# esp32-poe-thermocouple-hat-prod.net
KiCad netlist of a schematic drawn in EAGLE
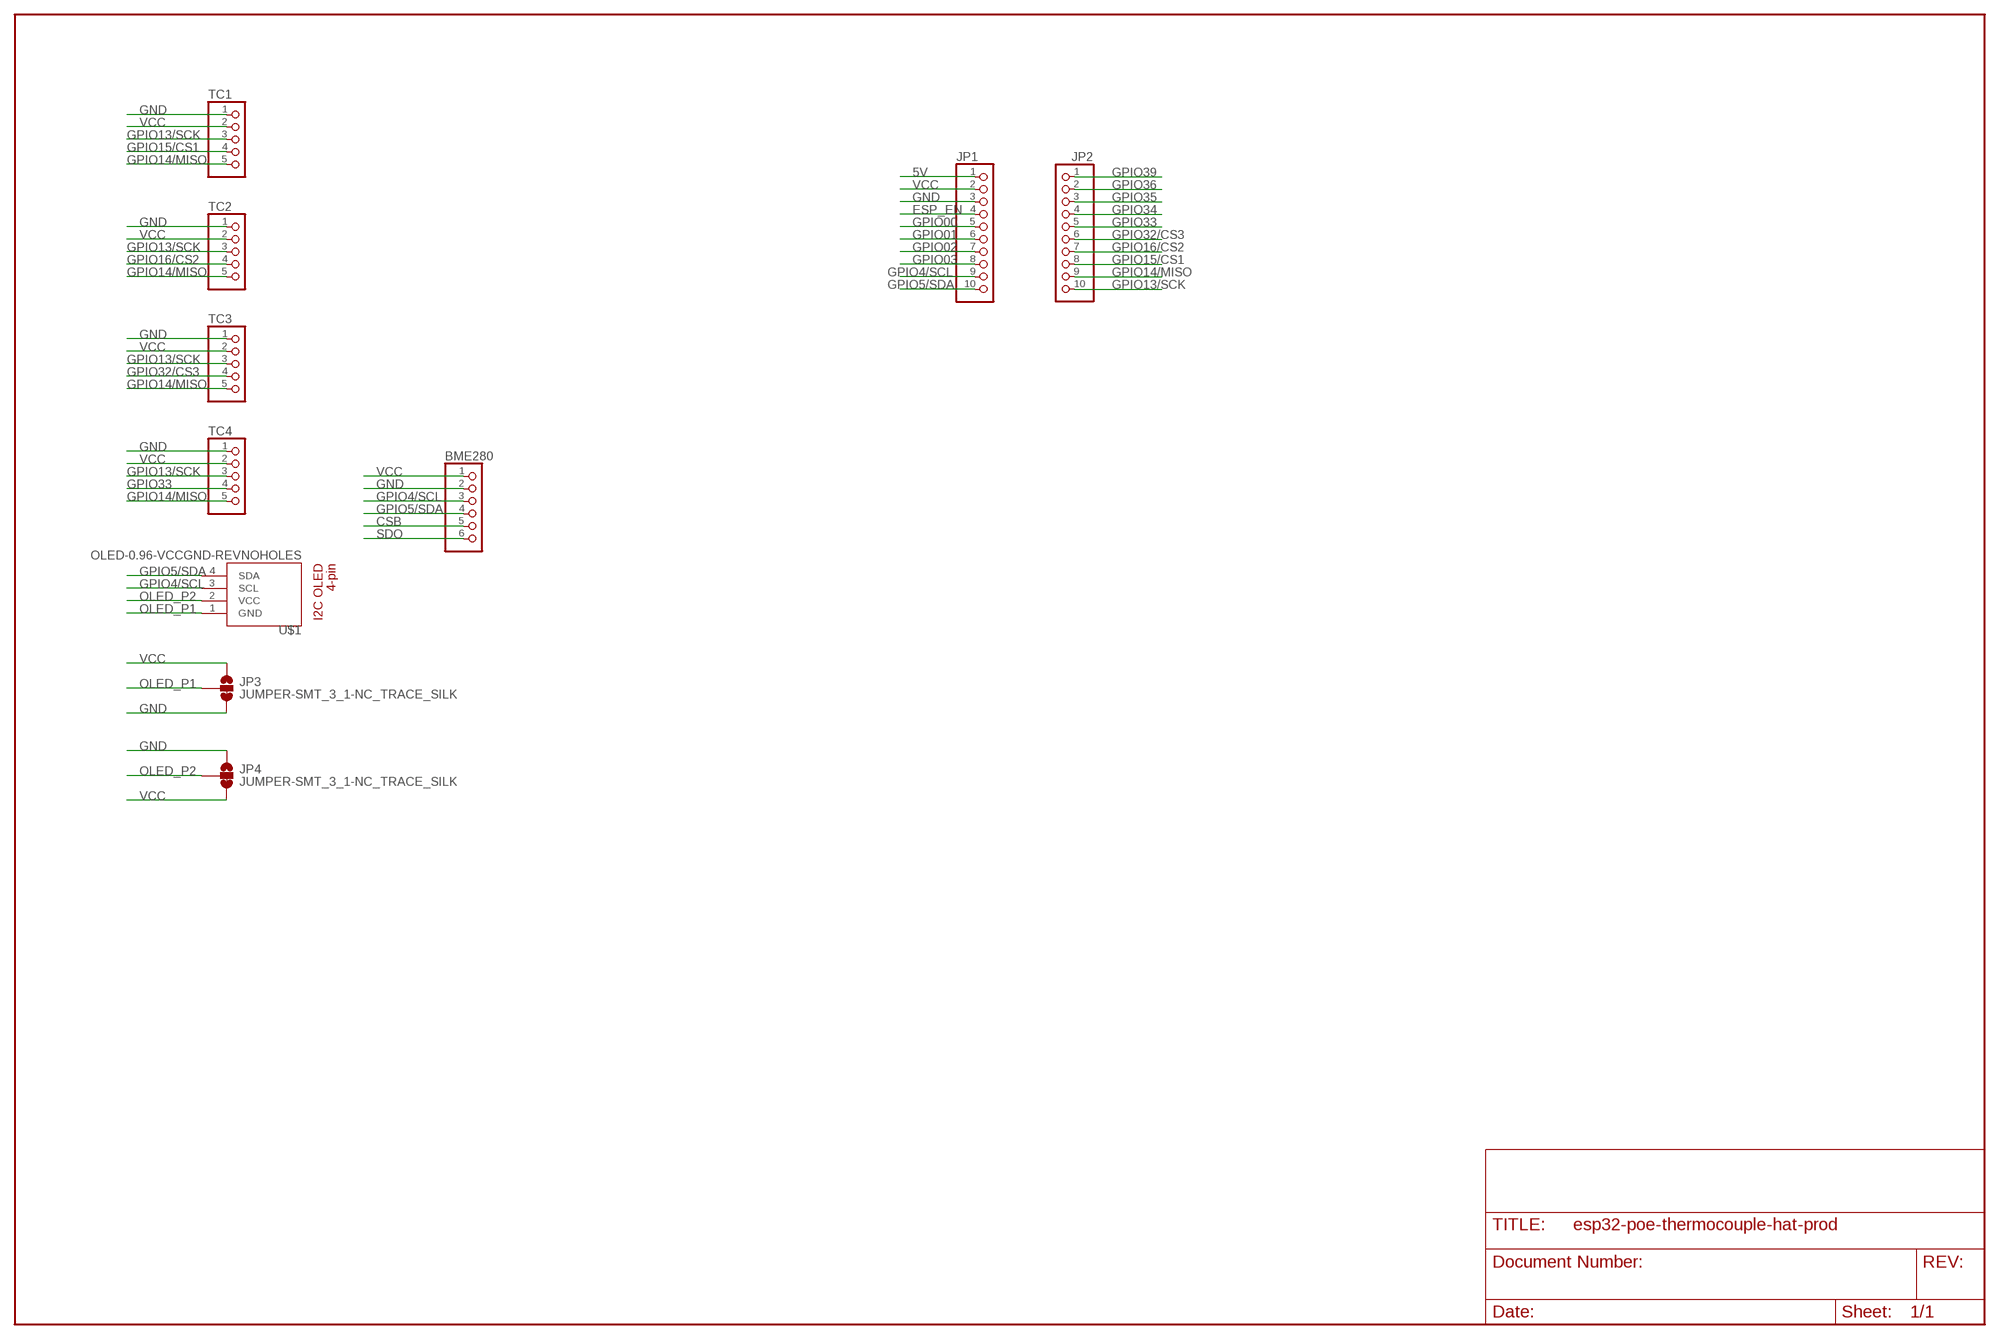
[diagram p0: schematic, sheet 1]

(export (version "E")
  (design (tool "Eeschema 10.0.6"))
  (components
    (comp (ref "BME280")
      (value "PINHD-1X6")
      (footprint "eagle-import:1X06")
      (libsource (lib "eagle-import") (part "PINHD-1X6"))
    )
    (comp (ref "JP1")
      (value "PINHD-1X10")
      (footprint "eagle-import:1X10")
      (libsource (lib "eagle-import") (part "PINHD-1X10"))
    )
    (comp (ref "JP2")
      (value "PINHD-1X10")
      (footprint "eagle-import:1X10")
      (libsource (lib "eagle-import") (part "PINHD-1X10"))
    )
    (comp (ref "JP3")
      (value "JUMPER-SMT_3_1-NC_TRACE_SILK")
      (footprint "eagle-import:SMT-JUMPER_3_1-NC_TRACE_SILK")
      (libsource (lib "eagle-import") (part "JUMPER-SMT_3_1-NC_TRACE_SILK"))
    )
    (comp (ref "JP4")
      (value "JUMPER-SMT_3_1-NC_TRACE_SILK")
      (footprint "eagle-import:SMT-JUMPER_3_1-NC_TRACE_SILK")
      (libsource (lib "eagle-import") (part "JUMPER-SMT_3_1-NC_TRACE_SILK"))
    )
    (comp (ref "TC1")
      (value "PINHD-1X5")
      (footprint "eagle-import:1X05")
      (libsource (lib "eagle-import") (part "PINHD-1X5"))
    )
    (comp (ref "TC2")
      (value "PINHD-1X5")
      (footprint "eagle-import:1X05")
      (libsource (lib "eagle-import") (part "PINHD-1X5"))
    )
    (comp (ref "TC3")
      (value "PINHD-1X5")
      (footprint "eagle-import:1X05")
      (libsource (lib "eagle-import") (part "PINHD-1X5"))
    )
    (comp (ref "TC4")
      (value "PINHD-1X5")
      (footprint "eagle-import:1X05")
      (libsource (lib "eagle-import") (part "PINHD-1X5"))
    )
    (comp (ref "U$1")
      (value "OLED-0.96-VCCGND-REVNOHOLES")
      (footprint "eagle-import:OLED-I2C-4PIN-NOHOLES")
      (libsource (lib "eagle-import") (part "OLED-0.96-VCCGND-REVNOHOLES"))
    )
  )
  (nets
    (net (code "1") (name "/5V") (class "Default")
      (node (ref "JP1") (pin "1") (pinfunction "1_1") (pintype "passive"))
    )
    (net (code "2") (name "/CSB") (class "Default")
      (node (ref "BME280") (pin "5") (pinfunction "5_5") (pintype "passive"))
    )
    (net (code "3") (name "/ESP_EN") (class "Default")
      (node (ref "JP1") (pin "4") (pinfunction "4_4") (pintype "passive"))
    )
    (net (code "4") (name "/GND") (class "Default")
      (node (ref "BME280") (pin "2") (pinfunction "2_2") (pintype "passive"))
      (node (ref "JP1") (pin "3") (pinfunction "3_3") (pintype "passive"))
      (node (ref "JP3") (pin "3") (pinfunction "3_3") (pintype "passive"))
      (node (ref "JP4") (pin "1") (pinfunction "1_1") (pintype "passive"))
      (node (ref "TC1") (pin "1") (pinfunction "1_1") (pintype "passive"))
      (node (ref "TC2") (pin "1") (pinfunction "1_1") (pintype "passive"))
      (node (ref "TC3") (pin "1") (pinfunction "1_1") (pintype "passive"))
      (node (ref "TC4") (pin "1") (pinfunction "1_1") (pintype "passive"))
    )
    (net (code "5") (name "/GPIO00") (class "Default")
      (node (ref "JP1") (pin "5") (pinfunction "5_5") (pintype "passive"))
    )
    (net (code "6") (name "/GPIO01") (class "Default")
      (node (ref "JP1") (pin "6") (pinfunction "6_6") (pintype "passive"))
    )
    (net (code "7") (name "/GPIO02") (class "Default")
      (node (ref "JP1") (pin "7") (pinfunction "7_7") (pintype "passive"))
    )
    (net (code "8") (name "/GPIO03") (class "Default")
      (node (ref "JP1") (pin "8") (pinfunction "8_8") (pintype "passive"))
    )
    (net (code "9") (name "/GPIO4{slash}SCL") (class "Default")
      (node (ref "BME280") (pin "3") (pinfunction "3_3") (pintype "passive"))
      (node (ref "JP1") (pin "9") (pinfunction "9_9") (pintype "passive"))
      (node (ref "U$1") (pin "3") (pinfunction "SCL_3") (pintype "bidirectional"))
    )
    (net (code "10") (name "/GPIO5{slash}SDA") (class "Default")
      (node (ref "BME280") (pin "4") (pinfunction "4_4") (pintype "passive"))
      (node (ref "JP1") (pin "10") (pinfunction "10_10") (pintype "passive"))
      (node (ref "U$1") (pin "4") (pinfunction "SDA_4") (pintype "bidirectional"))
    )
    (net (code "11") (name "/GPIO13{slash}SCK") (class "Default")
      (node (ref "JP2") (pin "10") (pinfunction "10_10") (pintype "passive"))
      (node (ref "TC1") (pin "3") (pinfunction "3_3") (pintype "passive"))
      (node (ref "TC2") (pin "3") (pinfunction "3_3") (pintype "passive"))
      (node (ref "TC3") (pin "3") (pinfunction "3_3") (pintype "passive"))
      (node (ref "TC4") (pin "3") (pinfunction "3_3") (pintype "passive"))
    )
    (net (code "12") (name "/GPIO14{slash}MISO") (class "Default")
      (node (ref "JP2") (pin "9") (pinfunction "9_9") (pintype "passive"))
      (node (ref "TC1") (pin "5") (pinfunction "5_5") (pintype "passive"))
      (node (ref "TC2") (pin "5") (pinfunction "5_5") (pintype "passive"))
      (node (ref "TC3") (pin "5") (pinfunction "5_5") (pintype "passive"))
      (node (ref "TC4") (pin "5") (pinfunction "5_5") (pintype "passive"))
    )
    (net (code "13") (name "/GPIO15{slash}CS1") (class "Default")
      (node (ref "JP2") (pin "8") (pinfunction "8_8") (pintype "passive"))
      (node (ref "TC1") (pin "4") (pinfunction "4_4") (pintype "passive"))
    )
    (net (code "14") (name "/GPIO16{slash}CS2") (class "Default")
      (node (ref "JP2") (pin "7") (pinfunction "7_7") (pintype "passive"))
      (node (ref "TC2") (pin "4") (pinfunction "4_4") (pintype "passive"))
    )
    (net (code "15") (name "/GPIO32{slash}CS3") (class "Default")
      (node (ref "JP2") (pin "6") (pinfunction "6_6") (pintype "passive"))
      (node (ref "TC3") (pin "4") (pinfunction "4_4") (pintype "passive"))
    )
    (net (code "16") (name "/GPIO33") (class "Default")
      (node (ref "JP2") (pin "5") (pinfunction "5_5") (pintype "passive"))
      (node (ref "TC4") (pin "4") (pinfunction "4_4") (pintype "passive"))
    )
    (net (code "17") (name "/GPIO34") (class "Default")
      (node (ref "JP2") (pin "4") (pinfunction "4_4") (pintype "passive"))
    )
    (net (code "18") (name "/GPIO35") (class "Default")
      (node (ref "JP2") (pin "3") (pinfunction "3_3") (pintype "passive"))
    )
    (net (code "19") (name "/GPIO36") (class "Default")
      (node (ref "JP2") (pin "2") (pinfunction "2_2") (pintype "passive"))
    )
    (net (code "20") (name "/GPIO39") (class "Default")
      (node (ref "JP2") (pin "1") (pinfunction "1_1") (pintype "passive"))
    )
    (net (code "21") (name "/OLED_P1") (class "Default")
      (node (ref "JP3") (pin "2") (pinfunction "2_2") (pintype "passive"))
      (node (ref "U$1") (pin "1") (pinfunction "GND_1") (pintype "bidirectional"))
    )
    (net (code "22") (name "/OLED_P2") (class "Default")
      (node (ref "JP4") (pin "2") (pinfunction "2_2") (pintype "passive"))
      (node (ref "U$1") (pin "2") (pinfunction "VCC_2") (pintype "bidirectional"))
    )
    (net (code "23") (name "/SDO") (class "Default")
      (node (ref "BME280") (pin "6") (pinfunction "6_6") (pintype "passive"))
    )
    (net (code "24") (name "/VCC") (class "Default")
      (node (ref "BME280") (pin "1") (pinfunction "1_1") (pintype "passive"))
      (node (ref "JP1") (pin "2") (pinfunction "2_2") (pintype "passive"))
      (node (ref "JP3") (pin "1") (pinfunction "1_1") (pintype "passive"))
      (node (ref "JP4") (pin "3") (pinfunction "3_3") (pintype "passive"))
      (node (ref "TC1") (pin "2") (pinfunction "2_2") (pintype "passive"))
      (node (ref "TC2") (pin "2") (pinfunction "2_2") (pintype "passive"))
      (node (ref "TC3") (pin "2") (pinfunction "2_2") (pintype "passive"))
      (node (ref "TC4") (pin "2") (pinfunction "2_2") (pintype "passive"))
    )
  )
)
